# POWER.net
KiCad netlist of a schematic drawn in Altium Designer
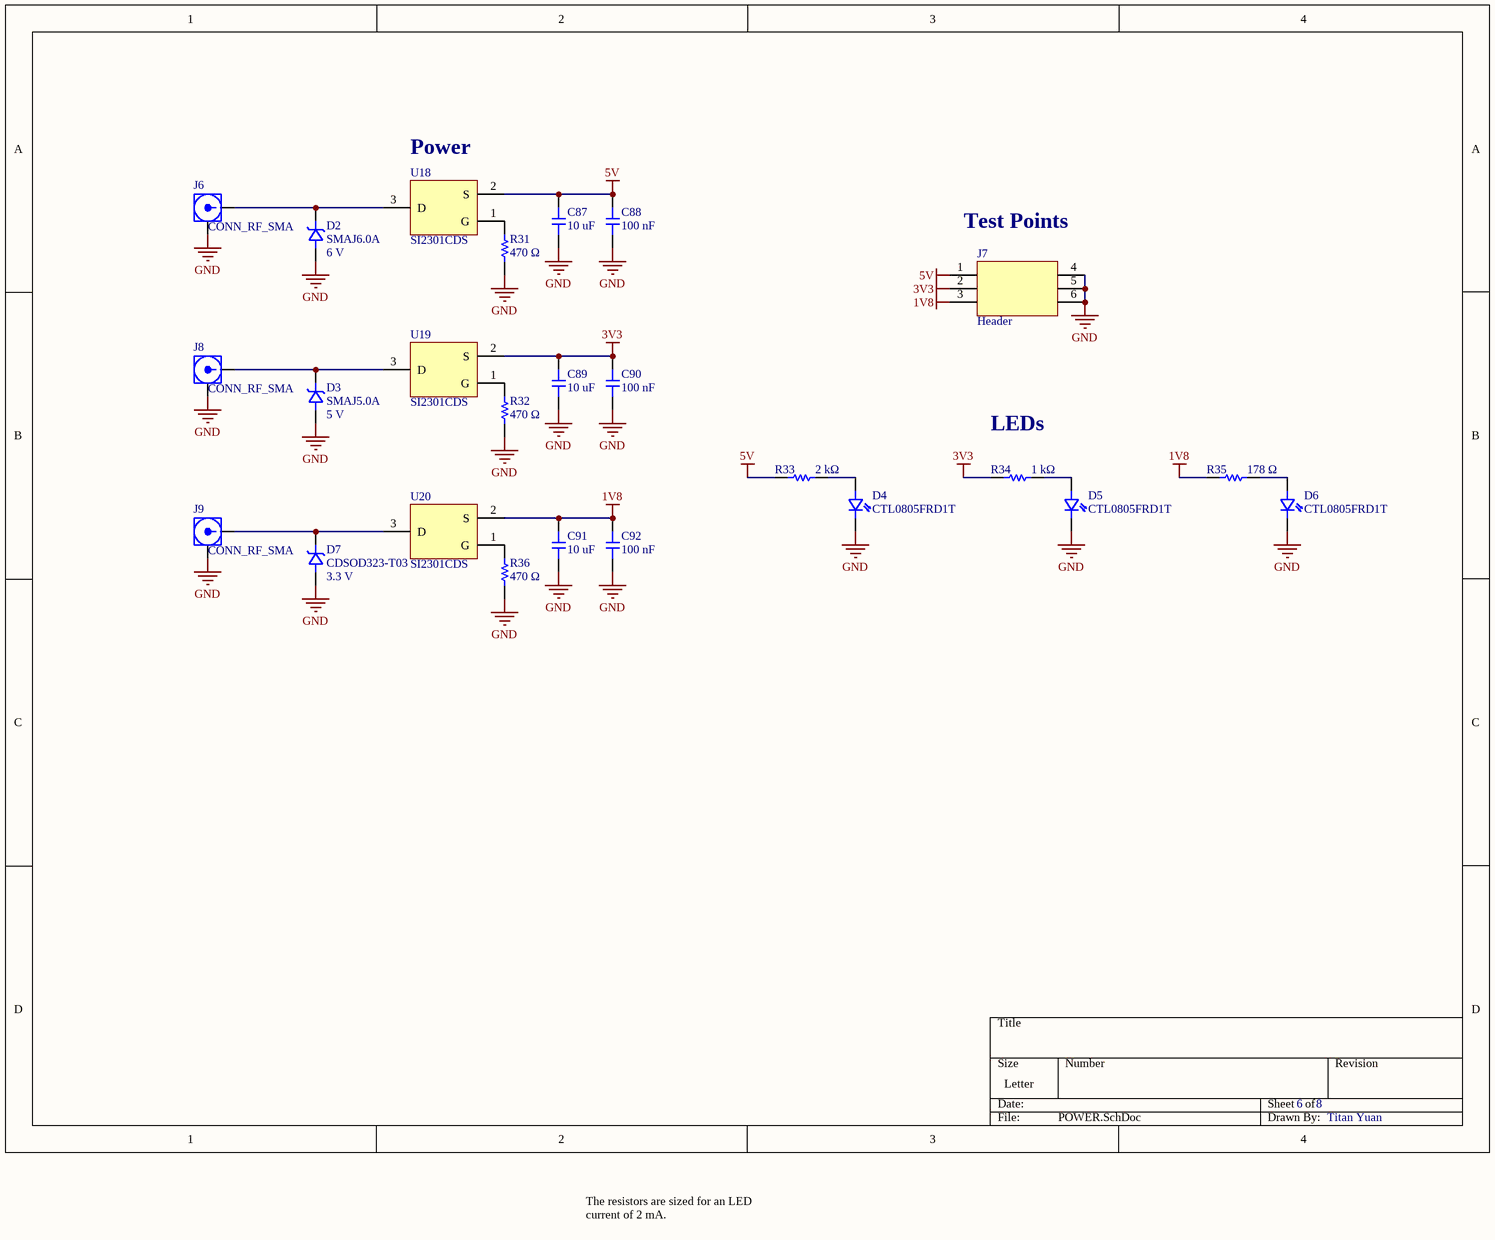
[diagram p0: POWER.SchDoc]

(export (version "E")
  (design (tool "Eeschema 10.0.6"))
  (components
    (comp (ref "C87")
      (value "10 uF")
      (footprint "CAP_0603")
      (description "10V 10uF X7R ±10% 0603 Multilayer Ceramic Capacitors MLCC - SMD/SMT ROHS")
      (fields
        (field (name "MANUFACTURER") "Murata Electronics")
        (field (name "MANUFACTURER PART NUMBER") "GRM188Z71A106KA73D")
      )
      (libsource (lib "Titan") (part "CAP"))
    )
    (comp (ref "C88")
      (value "100 nF")
      (footprint "CAP_0402")
      (description "Ceramic Capacitor, Ceramic, 50V, 10% +Tol, 10% -Tol, X7R, 15% TC, 0.1uF, Surface Mount, 0402")
      (fields
        (field (name "MANUFACTURER") "Yageo")
        (field (name "MANUFACTURER PART NUMBER") "CC0402KPX7R9BB104")
      )
      (libsource (lib "Titan") (part "CAP"))
    )
    (comp (ref "C89")
      (value "10 uF")
      (footprint "CAP_0603")
      (description "10V 10uF X7R ±10% 0603 Multilayer Ceramic Capacitors MLCC - SMD/SMT ROHS")
      (fields
        (field (name "MANUFACTURER") "Murata Electronics")
        (field (name "MANUFACTURER PART NUMBER") "GRM188Z71A106KA73D")
      )
      (libsource (lib "Titan") (part "CAP"))
    )
    (comp (ref "C90")
      (value "100 nF")
      (footprint "CAP_0402")
      (description "Ceramic Capacitor, Ceramic, 50V, 10% +Tol, 10% -Tol, X7R, 15% TC, 0.1uF, Surface Mount, 0402")
      (fields
        (field (name "MANUFACTURER") "Yageo")
        (field (name "MANUFACTURER PART NUMBER") "CC0402KPX7R9BB104")
      )
      (libsource (lib "Titan") (part "CAP"))
    )
    (comp (ref "C91")
      (value "10 uF")
      (footprint "CAP_0603")
      (description "10V 10uF X7R ±10% 0603 Multilayer Ceramic Capacitors MLCC - SMD/SMT ROHS")
      (fields
        (field (name "MANUFACTURER") "Murata Electronics")
        (field (name "MANUFACTURER PART NUMBER") "GRM188Z71A106KA73D")
      )
      (libsource (lib "Titan") (part "CAP"))
    )
    (comp (ref "C92")
      (value "100 nF")
      (footprint "CAP_0402")
      (description "Ceramic Capacitor, Ceramic, 50V, 10% +Tol, 10% -Tol, X7R, 15% TC, 0.1uF, Surface Mount, 0402")
      (fields
        (field (name "MANUFACTURER") "Yageo")
        (field (name "MANUFACTURER PART NUMBER") "CC0402KPX7R9BB104")
      )
      (libsource (lib "Titan") (part "CAP"))
    )
    (comp (ref "D2")
      (value "SMAJ6.0A")
      (footprint "SMAJ")
      (description "SMAJ Series 10.3 V 0.4 kW Surface Mount Uni-Directional TVS Diode - DO-214AC")
      (fields
        (field (name "MANUFACTURER") "Littelfuse Inc.")
        (field (name "REVERSE STANDOFF VOLTAGE") "6 V")
        (field (name "VOLTAGE") "60V")
      )
      (libsource (lib "Titan") (part "SMAJ6.0A"))
    )
    (comp (ref "D3")
      (value "SMAJ5.0A")
      (footprint "SMAJ")
      (description "SMAJ Series 9.2 V 400 W Surface Mount Uni-Directional TVS Diode - DO-214AC")
      (fields (field (name "MANUFACTURER") "Littelfuse Inc.") (field (name "REVERSE STANDOFF VOLTAGE") "5 V"))
      (libsource (lib "Titan") (part "SMAJ5.0A"))
    )
    (comp (ref "D4")
      (value "CTL0805FRD1T")
      (footprint "CTL0805FRD1T")
      (description "Chip Type LED, 0805, Flat Lens, Red")
      (fields
        (field (name "MANUFACTURER") "Venkel")
        (field (name "MANUFACTURER PART NUMBER") "CTL0805FRD1T-CT")
      )
      (libsource (lib "Titan") (part "CTL0805FRD1T"))
    )
    (comp (ref "D5")
      (value "CTL0805FRD1T")
      (footprint "CTL0805FRD1T")
      (description "Chip Type LED, 0805, Flat Lens, Red")
      (fields
        (field (name "MANUFACTURER") "Venkel")
        (field (name "MANUFACTURER PART NUMBER") "CTL0805FRD1T-CT")
      )
      (libsource (lib "Titan") (part "CTL0805FRD1T"))
    )
    (comp (ref "D6")
      (value "CTL0805FRD1T")
      (footprint "CTL0805FRD1T")
      (description "Chip Type LED, 0805, Flat Lens, Red")
      (fields
        (field (name "MANUFACTURER") "Venkel")
        (field (name "MANUFACTURER PART NUMBER") "CTL0805FRD1T-CT")
      )
      (libsource (lib "Titan") (part "CTL0805FRD1T"))
    )
    (comp (ref "D7")
      (value "CDSOD323-T03")
      (footprint "CDSOD323")
      (description "ESD protection diodes / TVS diodes; BOURNS; CDSOD323-T03; 19 V; 20 A; 3.3 V; 4 V")
      (fields (field (name "MANUFACTURER") "Bourns Inc.") (field (name "REVERSE STANDOFF VOLTAGE") "3.3 V"))
      (libsource (lib "Titan") (part "CDSOD323-T03"))
    )
    (comp (ref "J6")
      (value "CONN_RF_SMA")
      (footprint "142-0701-801")
      (description "RF / Coaxial Connector, SMA Coaxial, Straight Jack, Solder, 50 ohm, Beryllium Copper")
      (fields
        (field (name "MANUFACTURER") "Cinch Connectivity Solutions Johnson")
        (field (name "MANUFACTURER PART NUMBER") "142-0701-801")
      )
      (libsource (lib "Titan") (part "CONN_RF_SMA"))
    )
    (comp (ref "J7")
      (value "Header")
      (footprint "CONN_2x3_2.54mm_PinHeader_Vertical")
      (description "Pin Header, Board-to-Board, 2.54 mm, 2 Rows, 6 Contacts, Through Hole, TSW Series")
      (fields
        (field (name "MANUFACTURER") "Samtec")
        (field (name "MANUFACTURER PART NUMBER") "TSW-103-07-F-D")
      )
      (libsource (lib "Titan") (part "CONN_2x3_2.54mm_PinHeader_Vertical"))
    )
    (comp (ref "J8")
      (value "CONN_RF_SMA")
      (footprint "142-0701-801")
      (description "RF / Coaxial Connector, SMA Coaxial, Straight Jack, Solder, 50 ohm, Beryllium Copper")
      (fields
        (field (name "MANUFACTURER") "Cinch Connectivity Solutions Johnson")
        (field (name "MANUFACTURER PART NUMBER") "142-0701-801")
      )
      (libsource (lib "Titan") (part "CONN_RF_SMA"))
    )
    (comp (ref "J9")
      (value "CONN_RF_SMA")
      (footprint "142-0701-801")
      (description "RF / Coaxial Connector, SMA Coaxial, Straight Jack, Solder, 50 ohm, Beryllium Copper")
      (fields
        (field (name "MANUFACTURER") "Cinch Connectivity Solutions Johnson")
        (field (name "MANUFACTURER PART NUMBER") "142-0701-801")
      )
      (libsource (lib "Titan") (part "CONN_RF_SMA"))
    )
    (comp (ref "R31")
      (value "470 Ω")
      (footprint "RES_0402")
      (description "Res Thick Film 0402 470 Ohm 1% 0.063W(1/16W) ±100ppm/C Pad SMD T/R")
      (fields
        (field (name "MANUFACTURER") "Yageo")
        (field (name "MANUFACTURER PART NUMBER") "RC0402FR-07470RL")
      )
      (libsource (lib "Titan") (part "RES"))
    )
    (comp (ref "R32")
      (value "470 Ω")
      (footprint "RES_0402")
      (description "Res Thick Film 0402 470 Ohm 1% 0.063W(1/16W) ±100ppm/C Pad SMD T/R")
      (fields
        (field (name "MANUFACTURER") "Yageo")
        (field (name "MANUFACTURER PART NUMBER") "RC0402FR-07470RL")
      )
      (libsource (lib "Titan") (part "RES"))
    )
    (comp (ref "R33")
      (value "2 kΩ")
      (footprint "RES_0603")
      (description "100Mw Thick Film Resistors 100Ppm/ 1% 2K 0603 Chip Resistor Surface Mount Rohs")
      (fields
        (field (name "MANUFACTURER") "Yageo")
        (field (name "MANUFACTURER PART NUMBER") "RC0603FR-072KL")
      )
      (libsource (lib "Titan") (part "RES"))
    )
    (comp (ref "R34")
      (value "1 kΩ")
      (footprint "RES_0603")
      (description "100mW Thick Film Resistors 75V ±100ppm/℃ ±1% 1kΩ 0603 Chip Resistor - Surface Mount ROHS")
      (fields
        (field (name "MANUFACTURER") "Yageo")
        (field (name "MANUFACTURER PART NUMBER") "RC0603FR-071KL")
      )
      (libsource (lib "Titan") (part "RES"))
    )
    (comp (ref "R35")
      (value "178 Ω")
      (footprint "RES_0603")
      (description "Res Thick Film 0603 178 Ohm 1% 0.1W(1/10W) ±100ppm/C Pad SMD T/R")
      (fields
        (field (name "MANUFACTURER") "Yageo")
        (field (name "MANUFACTURER PART NUMBER") "RC0603FR-07178RL")
      )
      (libsource (lib "Titan") (part "RES"))
    )
    (comp (ref "R36")
      (value "470 Ω")
      (footprint "RES_0402")
      (description "Res Thick Film 0402 470 Ohm 1% 0.063W(1/16W) ±100ppm/C Pad SMD T/R")
      (fields
        (field (name "MANUFACTURER") "Yageo")
        (field (name "MANUFACTURER PART NUMBER") "RC0402FR-07470RL")
      )
      (libsource (lib "Titan") (part "RES"))
    )
    (comp (ref "U18")
      (value "SI2301CDS")
      (footprint "SI2301CDS")
      (description "P-ch Mosfet SOT-23 20V 112MOHM @ 4.5V - Lead(pb) And Halogen Free")
      (fields
        (field (name "MANUFACTURER") "Vishay Siliconix")
        (field (name "MANUFACTURER PART NUMBER") "SI2301CDS-T1-GE3")
      )
      (libsource (lib "Titan") (part "SI2301CDS"))
    )
    (comp (ref "U19")
      (value "SI2301CDS")
      (footprint "SI2301CDS")
      (description "P-ch Mosfet SOT-23 20V 112MOHM @ 4.5V - Lead(pb) And Halogen Free")
      (fields
        (field (name "MANUFACTURER") "Vishay Siliconix")
        (field (name "MANUFACTURER PART NUMBER") "SI2301CDS-T1-GE3")
      )
      (libsource (lib "Titan") (part "SI2301CDS"))
    )
    (comp (ref "U20")
      (value "SI2301CDS")
      (footprint "SI2301CDS")
      (description "P-ch Mosfet SOT-23 20V 112MOHM @ 4.5V - Lead(pb) And Halogen Free")
      (fields
        (field (name "MANUFACTURER") "Vishay Siliconix")
        (field (name "MANUFACTURER PART NUMBER") "SI2301CDS-T1-GE3")
      )
      (libsource (lib "Titan") (part "SI2301CDS"))
    )
  )
  (nets
    (net (code "1") (name "1V8") (class "Default")
      (node (ref "C91") (pin "2") (pintype "passive"))
      (node (ref "C92") (pin "2") (pintype "passive"))
      (node (ref "J7") (pin "3") (pintype "passive"))
      (node (ref "R35") (pin "1") (pintype "passive"))
      (node (ref "U20") (pin "2") (pinfunction "S_2") (pintype "passive"))
    )
    (net (code "2") (name "3V3") (class "Default")
      (node (ref "C89") (pin "2") (pintype "passive"))
      (node (ref "C90") (pin "2") (pintype "passive"))
      (node (ref "J7") (pin "2") (pintype "passive"))
      (node (ref "R34") (pin "1") (pintype "passive"))
      (node (ref "U19") (pin "2") (pinfunction "S_2") (pintype "passive"))
    )
    (net (code "3") (name "5V") (class "Default")
      (node (ref "C87") (pin "2") (pintype "passive"))
      (node (ref "C88") (pin "2") (pintype "passive"))
      (node (ref "J7") (pin "1") (pintype "passive"))
      (node (ref "R33") (pin "1") (pintype "passive"))
      (node (ref "U18") (pin "2") (pinfunction "S_2") (pintype "passive"))
    )
    (net (code "4") (name "GND") (class "Default")
      (node (ref "C87") (pin "1") (pintype "passive"))
      (node (ref "C88") (pin "1") (pintype "passive"))
      (node (ref "C89") (pin "1") (pintype "passive"))
      (node (ref "C90") (pin "1") (pintype "passive"))
      (node (ref "C91") (pin "1") (pintype "passive"))
      (node (ref "C92") (pin "1") (pintype "passive"))
      (node (ref "D2") (pin "2") (pintype "passive"))
      (node (ref "D3") (pin "2") (pintype "passive"))
      (node (ref "D4") (pin "1") (pintype "passive"))
      (node (ref "D5") (pin "1") (pintype "passive"))
      (node (ref "D6") (pin "1") (pintype "passive"))
      (node (ref "D7") (pin "2") (pintype "passive"))
      (node (ref "J6") (pin "2") (pintype "passive"))
      (node (ref "J7") (pin "4") (pintype "passive"))
      (node (ref "J7") (pin "5") (pintype "passive"))
      (node (ref "J7") (pin "6") (pintype "passive"))
      (node (ref "J8") (pin "2") (pintype "passive"))
      (node (ref "J9") (pin "2") (pintype "passive"))
      (node (ref "R31") (pin "1") (pintype "passive"))
      (node (ref "R32") (pin "1") (pintype "passive"))
      (node (ref "R36") (pin "1") (pintype "passive"))
    )
    (net (code "5") (name "Net-(D4-Pad2)") (class "Default")
      (node (ref "D4") (pin "2") (pintype "passive"))
      (node (ref "R33") (pin "2") (pintype "passive"))
    )
    (net (code "6") (name "Net-(D5-Pad2)") (class "Default")
      (node (ref "D5") (pin "2") (pintype "passive"))
      (node (ref "R34") (pin "2") (pintype "passive"))
    )
    (net (code "7") (name "Net-(D6-Pad2)") (class "Default")
      (node (ref "D6") (pin "2") (pintype "passive"))
      (node (ref "R35") (pin "2") (pintype "passive"))
    )
    (net (code "8") (name "Net-(U18-D)") (class "Default")
      (node (ref "D2") (pin "1") (pintype "passive"))
      (node (ref "J6") (pin "1") (pintype "passive"))
      (node (ref "U18") (pin "3") (pinfunction "D_3") (pintype "passive"))
    )
    (net (code "9") (name "Net-(U18-G)") (class "Default")
      (node (ref "R31") (pin "2") (pintype "passive"))
      (node (ref "U18") (pin "1") (pinfunction "G_1") (pintype "passive"))
    )
    (net (code "10") (name "Net-(U19-D)") (class "Default")
      (node (ref "D3") (pin "1") (pintype "passive"))
      (node (ref "J8") (pin "1") (pintype "passive"))
      (node (ref "U19") (pin "3") (pinfunction "D_3") (pintype "passive"))
    )
    (net (code "11") (name "Net-(U19-G)") (class "Default")
      (node (ref "R32") (pin "2") (pintype "passive"))
      (node (ref "U19") (pin "1") (pinfunction "G_1") (pintype "passive"))
    )
    (net (code "12") (name "Net-(U20-D)") (class "Default")
      (node (ref "D7") (pin "1") (pintype "passive"))
      (node (ref "J9") (pin "1") (pintype "passive"))
      (node (ref "U20") (pin "3") (pinfunction "D_3") (pintype "passive"))
    )
    (net (code "13") (name "Net-(U20-G)") (class "Default")
      (node (ref "R36") (pin "2") (pintype "passive"))
      (node (ref "U20") (pin "1") (pinfunction "G_1") (pintype "passive"))
    )
  )
)
